# MEMS_V3.net
KiCad netlist of a schematic drawn in Altium Designer
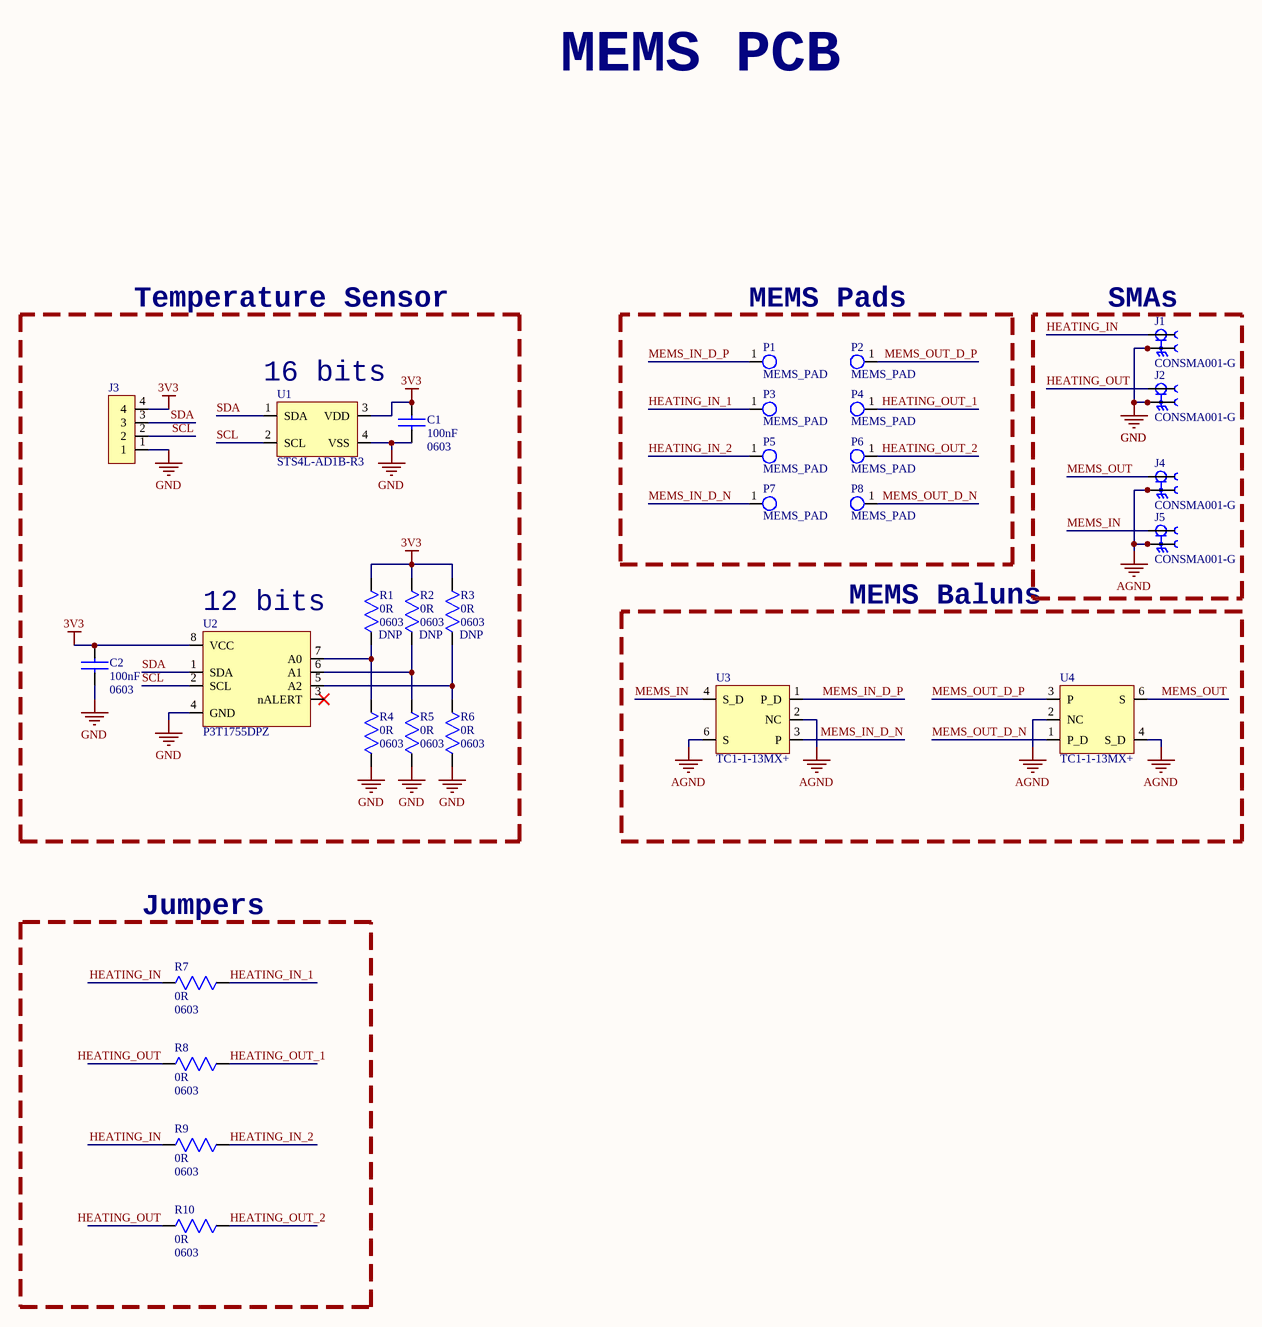
[diagram p0: MEMS_V3.SchDoc]

(export (version "E")
  (design (tool "Eeschema 10.0.6"))
  (components
    (comp (ref "C1")
      (value "100nF")
      (footprint "C0603")
      (description "CAP CER 100NF 100V X8L 0603")
      (fields
        (field (name "MANUFACTURER") "Samsung")
        (field (name "MANUFACTURER PART NUMBER") "CL10E104KC8VPNC")
        (field (name "CASE") "0603")
      )
      (libsource (lib "MEMS_LIB") (part "CL10E104KC8VPNC"))
    )
    (comp (ref "C2")
      (value "100nF")
      (footprint "C0603")
      (description "CAP CER 100NF 100V X8L 0603")
      (fields
        (field (name "MANUFACTURER") "Samsung")
        (field (name "MANUFACTURER PART NUMBER") "CL10E104KC8VPNC")
        (field (name "CASE") "0603")
      )
      (libsource (lib "MEMS_LIB") (part "CL10E104KC8VPNC"))
    )
    (comp (ref "J1")
      (value "CONSMA001-G")
      (footprint "CONSMA001-G")
      (description "CONN SMA RCPT STR 50 OHM PCB")
      (libsource (lib "MEMS_LIB") (part "CONSMA001-G"))
    )
    (comp (ref "J2")
      (value "CONSMA001-G")
      (footprint "CONSMA001-G")
      (description "CONN SMA RCPT STR 50 OHM PCB")
      (libsource (lib "MEMS_LIB") (part "CONSMA001-G"))
    )
    (comp (ref "J3")
      (value "61300411121")
      (footprint "WURTH_61300411121")
      (description "CONN HEADER VERT 4POS 2.54MM")
      (fields (field (name "MF") "WÃ¼rth Elektronik"))
      (libsource (lib "MEMS_LIB") (part "61300411121"))
    )
    (comp (ref "J4")
      (value "CONSMA001-G")
      (footprint "CONSMA001-G")
      (description "CONN SMA RCPT STR 50 OHM PCB")
      (libsource (lib "MEMS_LIB") (part "CONSMA001-G"))
    )
    (comp (ref "J5")
      (value "CONSMA001-G")
      (footprint "CONSMA001-G")
      (description "CONN SMA RCPT STR 50 OHM PCB")
      (libsource (lib "MEMS_LIB") (part "CONSMA001-G"))
    )
    (comp (ref "P1")
      (value "MEMS_PAD")
      (footprint "MEMS_PAD")
      (description "PAD MEMS connection")
      (libsource (lib "MEMS_LIB") (part "MEMS_PAD"))
    )
    (comp (ref "P2")
      (value "MEMS_PAD")
      (footprint "MEMS_PAD")
      (description "PAD MEMS connection")
      (libsource (lib "MEMS_LIB") (part "MEMS_PAD"))
    )
    (comp (ref "P3")
      (value "MEMS_PAD")
      (footprint "MEMS_PAD")
      (description "PAD MEMS connection")
      (libsource (lib "MEMS_LIB") (part "MEMS_PAD"))
    )
    (comp (ref "P4")
      (value "MEMS_PAD")
      (footprint "MEMS_PAD")
      (description "PAD MEMS connection")
      (libsource (lib "MEMS_LIB") (part "MEMS_PAD"))
    )
    (comp (ref "P5")
      (value "MEMS_PAD")
      (footprint "MEMS_PAD")
      (description "PAD MEMS connection")
      (libsource (lib "MEMS_LIB") (part "MEMS_PAD"))
    )
    (comp (ref "P6")
      (value "MEMS_PAD")
      (footprint "MEMS_PAD")
      (description "PAD MEMS connection")
      (libsource (lib "MEMS_LIB") (part "MEMS_PAD"))
    )
    (comp (ref "P7")
      (value "MEMS_PAD")
      (footprint "MEMS_PAD")
      (description "PAD MEMS connection")
      (libsource (lib "MEMS_LIB") (part "MEMS_PAD"))
    )
    (comp (ref "P8")
      (value "MEMS_PAD")
      (footprint "MEMS_PAD")
      (description "PAD MEMS connection")
      (libsource (lib "MEMS_LIB") (part "MEMS_PAD"))
    )
    (comp (ref "R1")
      (value "0R")
      (footprint "R0603")
      (description "RES 0 OHM JUMPER 1/10W 0603")
      (fields
        (field (name "MF") "Stackpole Electronics")
        (field (name "MP") "RMCF0603ZT0R00")
        (field (name "PACKAGE") "0603")
      )
      (libsource (lib "MEMS_LIB") (part "RMCF0603ZT0R00"))
    )
    (comp (ref "R2")
      (value "0R")
      (footprint "R0603")
      (description "RES 0 OHM JUMPER 1/10W 0603")
      (fields
        (field (name "MF") "Stackpole Electronics")
        (field (name "MP") "RMCF0603ZT0R00")
        (field (name "PACKAGE") "0603")
      )
      (libsource (lib "MEMS_LIB") (part "RMCF0603ZT0R00"))
    )
    (comp (ref "R3")
      (value "0R")
      (footprint "R0603")
      (description "RES 0 OHM JUMPER 1/10W 0603")
      (fields
        (field (name "MF") "Stackpole Electronics")
        (field (name "MP") "RMCF0603ZT0R00")
        (field (name "PACKAGE") "0603")
      )
      (libsource (lib "MEMS_LIB") (part "RMCF0603ZT0R00"))
    )
    (comp (ref "R4")
      (value "0R")
      (footprint "R0603")
      (description "RES 0 OHM JUMPER 1/10W 0603")
      (fields
        (field (name "MF") "Stackpole Electronics")
        (field (name "MP") "RMCF0603ZT0R00")
        (field (name "PACKAGE") "0603")
      )
      (libsource (lib "MEMS_LIB") (part "RMCF0603ZT0R00"))
    )
    (comp (ref "R5")
      (value "0R")
      (footprint "R0603")
      (description "RES 0 OHM JUMPER 1/10W 0603")
      (fields
        (field (name "MF") "Stackpole Electronics")
        (field (name "MP") "RMCF0603ZT0R00")
        (field (name "PACKAGE") "0603")
      )
      (libsource (lib "MEMS_LIB") (part "RMCF0603ZT0R00"))
    )
    (comp (ref "R6")
      (value "0R")
      (footprint "R0603")
      (description "RES 0 OHM JUMPER 1/10W 0603")
      (fields
        (field (name "MF") "Stackpole Electronics")
        (field (name "MP") "RMCF0603ZT0R00")
        (field (name "PACKAGE") "0603")
      )
      (libsource (lib "MEMS_LIB") (part "RMCF0603ZT0R00"))
    )
    (comp (ref "R7")
      (value "0R")
      (footprint "R0603")
      (description "RES 0 OHM JUMPER 1/10W 0603")
      (fields
        (field (name "MF") "Stackpole Electronics")
        (field (name "MP") "RMCF0603ZT0R00")
        (field (name "PACKAGE") "0603")
      )
      (libsource (lib "MEMS_LIB") (part "RMCF0603ZT0R00_1"))
    )
    (comp (ref "R8")
      (value "0R")
      (footprint "R0603")
      (description "RES 0 OHM JUMPER 1/10W 0603")
      (fields
        (field (name "MF") "Stackpole Electronics")
        (field (name "MP") "RMCF0603ZT0R00")
        (field (name "PACKAGE") "0603")
      )
      (libsource (lib "MEMS_LIB") (part "RMCF0603ZT0R00_1"))
    )
    (comp (ref "R9")
      (value "0R")
      (footprint "R0603")
      (description "RES 0 OHM JUMPER 1/10W 0603")
      (fields
        (field (name "MF") "Stackpole Electronics")
        (field (name "MP") "RMCF0603ZT0R00")
        (field (name "PACKAGE") "0603")
      )
      (libsource (lib "MEMS_LIB") (part "RMCF0603ZT0R00_1"))
    )
    (comp (ref "R10")
      (value "0R")
      (footprint "R0603")
      (description "RES 0 OHM JUMPER 1/10W 0603")
      (fields
        (field (name "MF") "Stackpole Electronics")
        (field (name "MP") "RMCF0603ZT0R00")
        (field (name "PACKAGE") "0603")
      )
      (libsource (lib "MEMS_LIB") (part "RMCF0603ZT0R00_1"))
    )
    (comp (ref "U1")
      (value "STS4L-AD1B-R3")
      (footprint "STS4L-AD1B-R3")
      (description "IC - TEMPERATURE SENSOR 4-DFN")
      (libsource (lib "MEMS_LIB") (part "STS4L-AD1B-R3"))
    )
    (comp (ref "U2")
      (value "P3T1755DPZ")
      (footprint "TSSOP8_P3T1755DPZ_NXP")
      (description "SENSOR DGTL -40C ~ 125C 8-TSSOP")
      (libsource (lib "MEMS_LIB") (part "P3T1755DPZ"))
    )
    (comp (ref "U3")
      (value "TC1-1-13MX+")
      (footprint "TC1-1-13MX+")
      (description "1:1 CORE & WIRE TRANSFORMER, 4.5")
      (libsource (lib "MEMS_LIB") (part "TC1-1-13MX+"))
    )
    (comp (ref "U4")
      (value "TC1-1-13MX+")
      (footprint "TC1-1-13MX+")
      (description "1:1 CORE & WIRE TRANSFORMER, 4.5")
      (libsource (lib "") (part "TC1-1-13MX+_1"))
    )
  )
  (nets
    (net (code "1") (name "/HEATING_IN") (class "Default")
      (node (ref "J1") (pin "1") (pinfunction "1_1") (pintype "passive"))
      (node (ref "R7") (pin "1") (pinfunction "1_1") (pintype "passive"))
      (node (ref "R9") (pin "1") (pinfunction "1_1") (pintype "passive"))
    )
    (net (code "2") (name "/HEATING_IN_1") (class "Default")
      (node (ref "P3") (pin "1") (pinfunction "1_1") (pintype "passive"))
      (node (ref "R7") (pin "2") (pinfunction "2_2") (pintype "passive"))
    )
    (net (code "3") (name "/HEATING_IN_2") (class "Default")
      (node (ref "P5") (pin "1") (pinfunction "1_1") (pintype "passive"))
      (node (ref "R9") (pin "2") (pinfunction "2_2") (pintype "passive"))
    )
    (net (code "4") (name "/HEATING_OUT") (class "Default")
      (node (ref "J2") (pin "1") (pinfunction "1_1") (pintype "passive"))
      (node (ref "R10") (pin "1") (pinfunction "1_1") (pintype "passive"))
      (node (ref "R8") (pin "1") (pinfunction "1_1") (pintype "passive"))
    )
    (net (code "5") (name "/HEATING_OUT_1") (class "Default")
      (node (ref "P4") (pin "1") (pinfunction "1_1") (pintype "passive"))
      (node (ref "R8") (pin "2") (pinfunction "2_2") (pintype "passive"))
    )
    (net (code "6") (name "/HEATING_OUT_2") (class "Default")
      (node (ref "P6") (pin "1") (pinfunction "1_1") (pintype "passive"))
      (node (ref "R10") (pin "2") (pinfunction "2_2") (pintype "passive"))
    )
    (net (code "7") (name "/MEMS_IN") (class "Default")
      (node (ref "J5") (pin "1") (pinfunction "1_1") (pintype "passive"))
      (node (ref "U3") (pin "4") (pinfunction "S_D_4") (pintype "passive"))
    )
    (net (code "8") (name "/MEMS_IN_D_N") (class "Default")
      (node (ref "P7") (pin "1") (pinfunction "1_1") (pintype "passive"))
      (node (ref "U3") (pin "3") (pinfunction "P_3") (pintype "passive"))
    )
    (net (code "9") (name "/MEMS_IN_D_P") (class "Default")
      (node (ref "P1") (pin "1") (pinfunction "1_1") (pintype "passive"))
      (node (ref "U3") (pin "1") (pinfunction "P_D_1") (pintype "passive"))
    )
    (net (code "10") (name "/MEMS_OUT") (class "Default")
      (node (ref "J4") (pin "1") (pinfunction "1_1") (pintype "passive"))
      (node (ref "U4") (pin "6") (pinfunction "S_6") (pintype "passive"))
    )
    (net (code "11") (name "/MEMS_OUT_D_N") (class "Default")
      (node (ref "P8") (pin "1") (pinfunction "1_1") (pintype "passive"))
      (node (ref "U4") (pin "1") (pinfunction "P_D_1") (pintype "passive"))
    )
    (net (code "12") (name "/MEMS_OUT_D_P") (class "Default")
      (node (ref "P2") (pin "1") (pinfunction "1_1") (pintype "passive"))
      (node (ref "U4") (pin "3") (pinfunction "P_3") (pintype "passive"))
    )
    (net (code "13") (name "/SCL") (class "Default")
      (node (ref "J3") (pin "2") (pinfunction "2_2") (pintype "passive"))
      (node (ref "U1") (pin "2") (pinfunction "SCL_2") (pintype "passive"))
      (node (ref "U2") (pin "2") (pinfunction "SCL_2") (pintype "passive"))
    )
    (net (code "14") (name "/SDA") (class "Default")
      (node (ref "J3") (pin "3") (pinfunction "3_3") (pintype "passive"))
      (node (ref "U1") (pin "1") (pinfunction "SDA_1") (pintype "passive"))
      (node (ref "U2") (pin "1") (pinfunction "SDA_1") (pintype "passive"))
    )
    (net (code "15") (name "3V3") (class "Default")
      (node (ref "C1") (pin "1") (pinfunction "1_1") (pintype "passive"))
      (node (ref "C2") (pin "1") (pinfunction "1_1") (pintype "passive"))
      (node (ref "J3") (pin "4") (pinfunction "4_4") (pintype "passive"))
      (node (ref "R1") (pin "2") (pinfunction "2_2") (pintype "passive"))
      (node (ref "R2") (pin "2") (pinfunction "2_2") (pintype "passive"))
      (node (ref "R3") (pin "2") (pinfunction "2_2") (pintype "passive"))
      (node (ref "U1") (pin "3") (pinfunction "VDD_3") (pintype "passive"))
      (node (ref "U2") (pin "8") (pinfunction "VCC_8") (pintype "power_in"))
    )
    (net (code "16") (name "AGND") (class "Default")
      (node (ref "J4") (pin "S1") (pinfunction "2_S1") (pintype "passive"))
      (node (ref "J4") (pin "S2") (pinfunction "2_S2") (pintype "passive"))
      (node (ref "J4") (pin "S3") (pinfunction "2_S3") (pintype "passive"))
      (node (ref "J4") (pin "S4") (pinfunction "2_S4") (pintype "passive"))
      (node (ref "J5") (pin "S1") (pinfunction "2_S1") (pintype "passive"))
      (node (ref "J5") (pin "S2") (pinfunction "2_S2") (pintype "passive"))
      (node (ref "J5") (pin "S3") (pinfunction "2_S3") (pintype "passive"))
      (node (ref "J5") (pin "S4") (pinfunction "2_S4") (pintype "passive"))
      (node (ref "U3") (pin "2") (pinfunction "NC_2") (pintype "passive"))
      (node (ref "U3") (pin "6") (pinfunction "S_6") (pintype "passive"))
      (node (ref "U4") (pin "2") (pinfunction "NC_2") (pintype "passive"))
      (node (ref "U4") (pin "4") (pinfunction "S_D_4") (pintype "passive"))
    )
    (net (code "17") (name "GND") (class "Default")
      (node (ref "C1") (pin "2") (pinfunction "2_2") (pintype "passive"))
      (node (ref "C2") (pin "2") (pinfunction "2_2") (pintype "passive"))
      (node (ref "J1") (pin "S1") (pinfunction "2_S1") (pintype "passive"))
      (node (ref "J1") (pin "S2") (pinfunction "2_S2") (pintype "passive"))
      (node (ref "J1") (pin "S3") (pinfunction "2_S3") (pintype "passive"))
      (node (ref "J1") (pin "S4") (pinfunction "2_S4") (pintype "passive"))
      (node (ref "J2") (pin "S1") (pinfunction "2_S1") (pintype "passive"))
      (node (ref "J2") (pin "S2") (pinfunction "2_S2") (pintype "passive"))
      (node (ref "J2") (pin "S3") (pinfunction "2_S3") (pintype "passive"))
      (node (ref "J2") (pin "S4") (pinfunction "2_S4") (pintype "passive"))
      (node (ref "J3") (pin "1") (pinfunction "1_1") (pintype "passive"))
      (node (ref "R4") (pin "1") (pinfunction "1_1") (pintype "passive"))
      (node (ref "R5") (pin "1") (pinfunction "1_1") (pintype "passive"))
      (node (ref "R6") (pin "1") (pinfunction "1_1") (pintype "passive"))
      (node (ref "U1") (pin "4") (pinfunction "VSS_4") (pintype "passive"))
      (node (ref "U2") (pin "4") (pinfunction "GND_4") (pintype "power_in"))
    )
    (net (code "18") (name "Net-(U2-A0)") (class "Default")
      (node (ref "R1") (pin "1") (pinfunction "1_1") (pintype "passive"))
      (node (ref "R4") (pin "2") (pinfunction "2_2") (pintype "passive"))
      (node (ref "U2") (pin "7") (pinfunction "A0_7") (pintype "passive"))
    )
    (net (code "19") (name "Net-(U2-A1)") (class "Default")
      (node (ref "R2") (pin "1") (pinfunction "1_1") (pintype "passive"))
      (node (ref "R5") (pin "2") (pinfunction "2_2") (pintype "passive"))
      (node (ref "U2") (pin "6") (pinfunction "A1_6") (pintype "passive"))
    )
    (net (code "20") (name "Net-(U2-A2)") (class "Default")
      (node (ref "R3") (pin "1") (pinfunction "1_1") (pintype "passive"))
      (node (ref "R6") (pin "2") (pinfunction "2_2") (pintype "passive"))
      (node (ref "U2") (pin "5") (pinfunction "A2_5") (pintype "passive"))
    )
    (net (code "21") (name "unconnected-(U2-nALERT-Pad3)") (class "Default")
      (node (ref "U2") (pin "3") (pinfunction "nALERT_3") (pintype "passive+no_connect"))
    )
  )
)
